# tracker03-12.net
KiCad netlist of a schematic drawn in EAGLE
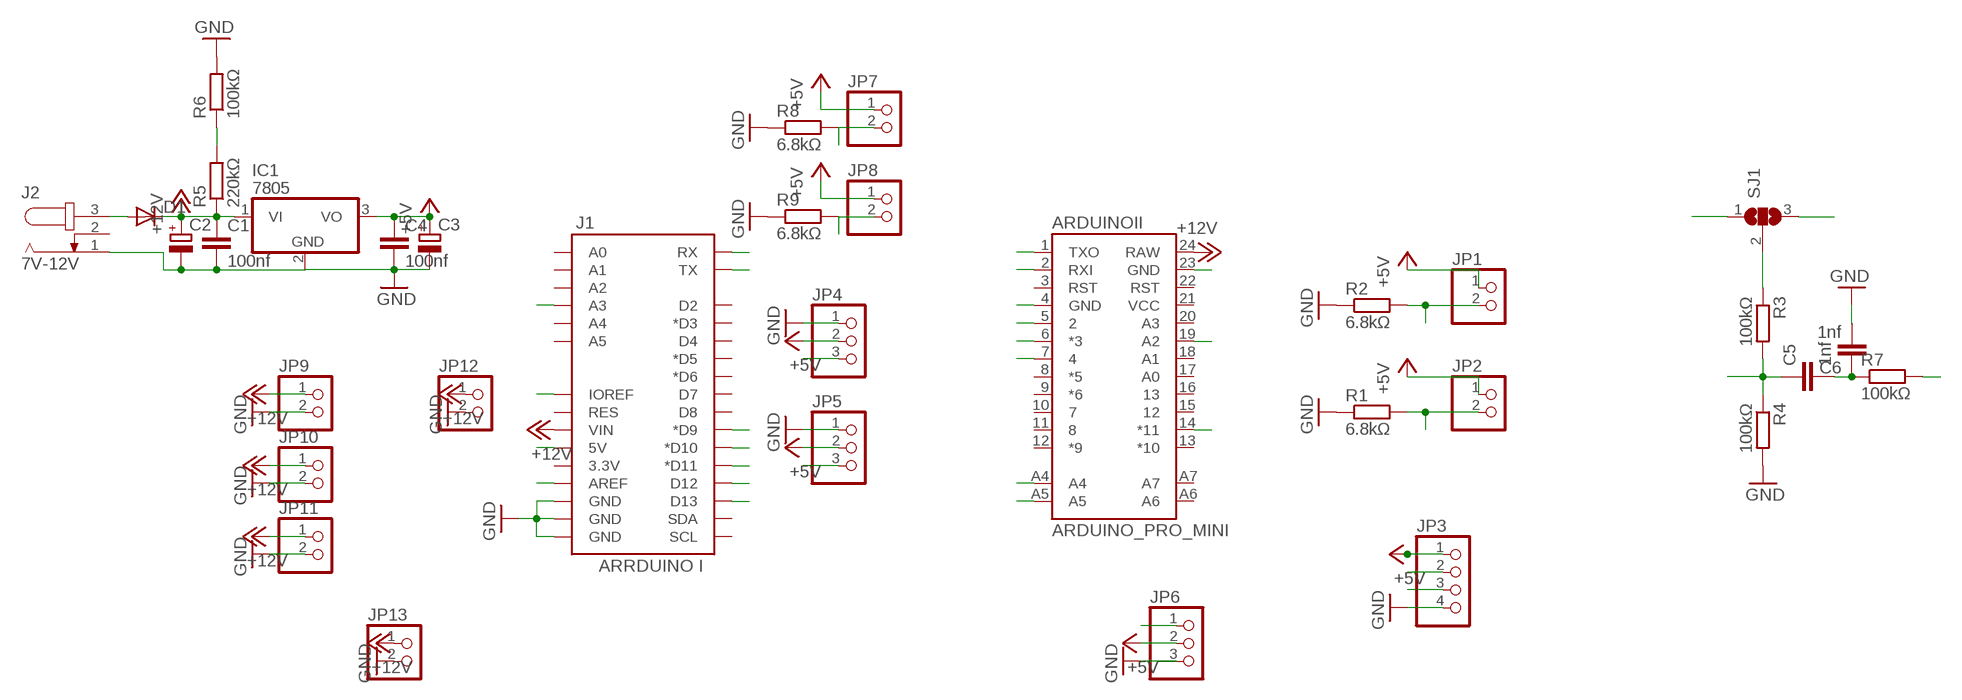
[diagram p0: schematic, sheet 1]

(export (version "E")
  (design (tool "Eeschema 10.0.6"))
  (components
    (comp (ref "ARDUINOII")
      (value "ARDUINO_PRO_MINI")
      (footprint "eagle-import:ARDUINO_PRO_MINI")
      (libsource (lib "eagle-import") (part "ARDUINO_PRO_MINI"))
    )
    (comp (ref "C1")
      (value "100nf")
      (footprint "eagle-import:C050-025X075")
      (libsource (lib "eagle-import") (part "C-EU050-025X075"))
    )
    (comp (ref "C2")
      (value "CPOL-EUE3.5-8")
      (footprint "eagle-import:E3,5-8")
      (libsource (lib "eagle-import") (part "CPOL-EUE3.5-8"))
    )
    (comp (ref "C3")
      (value "CPOL-EUE2.5-5")
      (footprint "eagle-import:E2,5-5")
      (libsource (lib "eagle-import") (part "CPOL-EUE2.5-5"))
    )
    (comp (ref "C4")
      (value "100nf")
      (footprint "eagle-import:C050-025X075")
      (libsource (lib "eagle-import") (part "C-EU050-025X075"))
    )
    (comp (ref "C5")
      (value "1nf")
      (footprint "eagle-import:C050-025X075")
      (libsource (lib "eagle-import") (part "C-EU050-025X075"))
    )
    (comp (ref "C6")
      (value "1nf")
      (footprint "eagle-import:C050-025X075")
      (libsource (lib "eagle-import") (part "C-EU050-025X075"))
    )
    (comp (ref "D1")
      (value "1N4004")
      (footprint "eagle-import:DO41-10")
      (libsource (lib "eagle-import") (part "1N4004"))
    )
    (comp (ref "IC1")
      (value "7805")
      (footprint "eagle-import:TO220V")
      (libsource (lib "eagle-import") (part "78TV05"))
    )
    (comp (ref "J1")
      (value "ARRDUINO I")
      (footprint "eagle-import:UNO_R3_SHIELD_NOLABELS")
      (libsource (lib "eagle-import") (part "ARDUINO_R3_SHIELDNOLABELS"))
    )
    (comp (ref "J2")
      (value "7V-12V")
      (footprint "eagle-import:SPC4077")
      (libsource (lib "eagle-import") (part "JACK-PLUG0"))
    )
    (comp (ref "JP1")
      (value "PINHD-1X2")
      (footprint "eagle-import:1X02")
      (libsource (lib "eagle-import") (part "PINHD-1X2"))
    )
    (comp (ref "JP2")
      (value "PINHD-1X2")
      (footprint "eagle-import:1X02")
      (libsource (lib "eagle-import") (part "PINHD-1X2"))
    )
    (comp (ref "JP3")
      (value "PINHD-1X4")
      (footprint "eagle-import:1X04")
      (libsource (lib "eagle-import") (part "PINHD-1X4"))
    )
    (comp (ref "JP4")
      (value "PINHD-1X3")
      (footprint "eagle-import:1X03")
      (libsource (lib "eagle-import") (part "PINHD-1X3"))
    )
    (comp (ref "JP5")
      (value "PINHD-1X3")
      (footprint "eagle-import:1X03")
      (libsource (lib "eagle-import") (part "PINHD-1X3"))
    )
    (comp (ref "JP6")
      (value "PINHD-1X3")
      (footprint "eagle-import:1X03")
      (libsource (lib "eagle-import") (part "PINHD-1X3"))
    )
    (comp (ref "JP7")
      (value "PINHD-1X2")
      (footprint "eagle-import:1X02")
      (libsource (lib "eagle-import") (part "PINHD-1X2"))
    )
    (comp (ref "JP8")
      (value "PINHD-1X2")
      (footprint "eagle-import:1X02")
      (libsource (lib "eagle-import") (part "PINHD-1X2"))
    )
    (comp (ref "JP9")
      (value "PINHD-1X2")
      (footprint "eagle-import:1X02")
      (libsource (lib "eagle-import") (part "PINHD-1X2"))
    )
    (comp (ref "JP10")
      (value "PINHD-1X2")
      (footprint "eagle-import:1X02")
      (libsource (lib "eagle-import") (part "PINHD-1X2"))
    )
    (comp (ref "JP11")
      (value "PINHD-1X2")
      (footprint "eagle-import:1X02")
      (libsource (lib "eagle-import") (part "PINHD-1X2"))
    )
    (comp (ref "JP12")
      (value "PINHD-1X2")
      (footprint "eagle-import:1X02")
      (libsource (lib "eagle-import") (part "PINHD-1X2"))
    )
    (comp (ref "JP13")
      (value "PINHD-1X2")
      (footprint "eagle-import:1X02")
      (libsource (lib "eagle-import") (part "PINHD-1X2"))
    )
    (comp (ref "R1")
      (value "6.8kΩ")
      (footprint "eagle-import:0204V")
      (libsource (lib "eagle-import") (part "R-EU_0204/2V"))
    )
    (comp (ref "R2")
      (value "6.8kΩ")
      (footprint "eagle-import:0204V")
      (libsource (lib "eagle-import") (part "R-EU_0204/2V"))
    )
    (comp (ref "R3")
      (value "100kΩ")
      (footprint "eagle-import:0204V")
      (libsource (lib "eagle-import") (part "R-EU_0204/2V"))
    )
    (comp (ref "R4")
      (value "100kΩ")
      (footprint "eagle-import:0204V")
      (libsource (lib "eagle-import") (part "R-EU_0204/2V"))
    )
    (comp (ref "R5")
      (value "220kΩ")
      (footprint "eagle-import:0204V")
      (libsource (lib "eagle-import") (part "R-EU_0204/2V"))
    )
    (comp (ref "R6")
      (value "100kΩ")
      (footprint "eagle-import:0204V")
      (libsource (lib "eagle-import") (part "R-EU_0204/2V"))
    )
    (comp (ref "R7")
      (value "100kΩ")
      (footprint "eagle-import:0204V")
      (libsource (lib "eagle-import") (part "R-EU_0204/2V"))
    )
    (comp (ref "R8")
      (value "6.8kΩ")
      (footprint "eagle-import:0204V")
      (libsource (lib "eagle-import") (part "R-EU_0204/2V"))
    )
    (comp (ref "R9")
      (value "6.8kΩ")
      (footprint "eagle-import:0204V")
      (libsource (lib "eagle-import") (part "R-EU_0204/2V"))
    )
    (comp (ref "SJ1")
      (value "SJ2W")
      (footprint "eagle-import:SJ_2")
      (libsource (lib "eagle-import") (part "SJ2W"))
    )
  )
  (nets
    (net (code "1") (name "+5V") (class "Default")
      (node (ref "C3") (pin "+") (pinfunction "+_+") (pintype "passive"))
      (node (ref "C4") (pin "1") (pinfunction "1_1") (pintype "passive"))
      (node (ref "IC1") (pin "3") (pinfunction "VO_3") (pintype "passive"))
      (node (ref "JP1") (pin "1") (pinfunction "1_1") (pintype "passive"))
      (node (ref "JP2") (pin "1") (pinfunction "1_1") (pintype "passive"))
      (node (ref "JP3") (pin "1") (pinfunction "1_1") (pintype "passive"))
      (node (ref "JP4") (pin "2") (pinfunction "2_2") (pintype "passive"))
      (node (ref "JP5") (pin "2") (pinfunction "2_2") (pintype "passive"))
      (node (ref "JP6") (pin "2") (pinfunction "2_2") (pintype "passive"))
      (node (ref "JP7") (pin "1") (pinfunction "1_1") (pintype "passive"))
      (node (ref "JP8") (pin "1") (pinfunction "1_1") (pintype "passive"))
    )
    (net (code "2") (name "+12V") (class "Default")
      (node (ref "ARDUINOII") (pin "24") (pinfunction "RAW_24") (pintype "bidirectional"))
      (node (ref "C1") (pin "1") (pinfunction "1_1") (pintype "passive"))
      (node (ref "C2") (pin "+") (pinfunction "+_+") (pintype "passive"))
      (node (ref "D1") (pin "C") (pinfunction "C_C") (pintype "passive"))
      (node (ref "IC1") (pin "1") (pinfunction "VI_1") (pintype "input"))
      (node (ref "J1") (pin "VIN") (pinfunction "VIN_VIN") (pintype "bidirectional"))
      (node (ref "JP10") (pin "1") (pinfunction "1_1") (pintype "passive"))
      (node (ref "JP11") (pin "1") (pinfunction "1_1") (pintype "passive"))
      (node (ref "JP12") (pin "1") (pinfunction "1_1") (pintype "passive"))
      (node (ref "JP13") (pin "1") (pinfunction "1_1") (pintype "passive"))
      (node (ref "JP9") (pin "1") (pinfunction "1_1") (pintype "passive"))
      (node (ref "R5") (pin "1") (pinfunction "1_1") (pintype "passive"))
    )
    (net (code "3") (name "/5VA") (class "Default")
      (node (ref "J1") (pin "5V") (pinfunction "5V_5V") (pintype "bidirectional"))
      (node (ref "SJ1") (pin "3") (pinfunction "3_3") (pintype "passive"))
    )
    (net (code "4") (name "/A2") (class "Default")
      (node (ref "ARDUINOII") (pin "19") (pinfunction "A2_19") (pintype "bidirectional"))
      (node (ref "R5") (pin "2") (pinfunction "2_2") (pintype "passive"))
      (node (ref "R6") (pin "1") (pinfunction "1_1") (pintype "passive"))
    )
    (net (code "5") (name "/A3") (class "Default")
      (node (ref "C5") (pin "1") (pinfunction "1_1") (pintype "passive"))
      (node (ref "J1") (pin "A3") (pinfunction "A3_A3") (pintype "bidirectional"))
      (node (ref "R3") (pin "2") (pinfunction "2_2") (pintype "passive"))
      (node (ref "R4") (pin "1") (pinfunction "1_1") (pintype "passive"))
    )
    (net (code "6") (name "/A4") (class "Default")
      (node (ref "ARDUINOII") (pin "A4") (pinfunction "A4_A4") (pintype "bidirectional"))
      (node (ref "JP3") (pin "2") (pinfunction "2_2") (pintype "passive"))
    )
    (net (code "7") (name "/A5") (class "Default")
      (node (ref "ARDUINOII") (pin "A5") (pinfunction "A5_A5") (pintype "bidirectional"))
      (node (ref "JP3") (pin "3") (pinfunction "3_3") (pintype "passive"))
    )
    (net (code "8") (name "/AREF") (class "Default")
      (node (ref "J1") (pin "AREF") (pinfunction "AREF_AREF") (pintype "bidirectional"))
      (node (ref "SJ1") (pin "1") (pinfunction "1_1") (pintype "passive"))
    )
    (net (code "9") (name "/D2") (class "Default")
      (node (ref "ARDUINOII") (pin "5") (pinfunction "2_5") (pintype "bidirectional"))
      (node (ref "JP1") (pin "2") (pinfunction "2_2") (pintype "passive"))
      (node (ref "R2") (pin "2") (pinfunction "2_2") (pintype "passive"))
    )
    (net (code "10") (name "/D4") (class "Default")
      (node (ref "ARDUINOII") (pin "7") (pinfunction "4_7") (pintype "bidirectional"))
      (node (ref "JP2") (pin "2") (pinfunction "2_2") (pintype "passive"))
      (node (ref "R1") (pin "2") (pinfunction "2_2") (pintype "passive"))
    )
    (net (code "11") (name "/D9") (class "Default")
      (node (ref "J1") (pin "D9") (pinfunction "*D9_D9") (pintype "bidirectional"))
      (node (ref "JP4") (pin "3") (pinfunction "3_3") (pintype "passive"))
    )
    (net (code "12") (name "/D10") (class "Default")
      (node (ref "J1") (pin "D10") (pinfunction "*D10_D10") (pintype "bidirectional"))
      (node (ref "JP5") (pin "3") (pinfunction "3_3") (pintype "passive"))
    )
    (net (code "13") (name "/D11") (class "Default")
      (node (ref "ARDUINOII") (pin "14") (pinfunction "*11_14") (pintype "bidirectional"))
      (node (ref "JP6") (pin "1") (pinfunction "1_1") (pintype "passive"))
    )
    (net (code "14") (name "/D11A1") (class "Default")
      (node (ref "J1") (pin "D11") (pinfunction "*D11_D11") (pintype "bidirectional"))
      (node (ref "JP7") (pin "2") (pinfunction "2_2") (pintype "passive"))
      (node (ref "R8") (pin "2") (pinfunction "2_2") (pintype "passive"))
    )
    (net (code "15") (name "/D12") (class "Default")
      (node (ref "J1") (pin "D12") (pinfunction "D12_D12") (pintype "bidirectional"))
      (node (ref "JP8") (pin "2") (pinfunction "2_2") (pintype "passive"))
      (node (ref "R9") (pin "2") (pinfunction "2_2") (pintype "passive"))
    )
    (net (code "16") (name "/RX") (class "Default")
      (node (ref "ARDUINOII") (pin "1") (pinfunction "TXO_1") (pintype "bidirectional"))
      (node (ref "J1") (pin "RX") (pinfunction "RX_RX") (pintype "bidirectional"))
    )
    (net (code "17") (name "/TX") (class "Default")
      (node (ref "ARDUINOII") (pin "2") (pinfunction "RXI_2") (pintype "bidirectional"))
      (node (ref "J1") (pin "TX") (pinfunction "TX_TX") (pintype "bidirectional"))
    )
    (net (code "18") (name "GND") (class "Default")
      (node (ref "ARDUINOII") (pin "23") (pinfunction "GND_23") (pintype "bidirectional"))
      (node (ref "ARDUINOII") (pin "4") (pinfunction "GND_4") (pintype "bidirectional"))
      (node (ref "C1") (pin "2") (pinfunction "2_2") (pintype "passive"))
      (node (ref "C2") (pin "-") (pinfunction "-_-") (pintype "passive"))
      (node (ref "C3") (pin "-") (pinfunction "-_-") (pintype "passive"))
      (node (ref "C4") (pin "2") (pinfunction "2_2") (pintype "passive"))
      (node (ref "C6") (pin "2") (pinfunction "2_2") (pintype "passive"))
      (node (ref "IC1") (pin "2") (pinfunction "GND_2") (pintype "passive"))
      (node (ref "J1") (pin "GND@0") (pinfunction "GND_GND@0") (pintype "bidirectional"))
      (node (ref "J1") (pin "GND@1") (pinfunction "GND_GND@1") (pintype "bidirectional"))
      (node (ref "J1") (pin "GND@2") (pinfunction "GND_GND@2") (pintype "bidirectional"))
      (node (ref "J2") (pin "1") (pinfunction "1_1") (pintype "passive"))
      (node (ref "JP10") (pin "2") (pinfunction "2_2") (pintype "passive"))
      (node (ref "JP11") (pin "2") (pinfunction "2_2") (pintype "passive"))
      (node (ref "JP12") (pin "2") (pinfunction "2_2") (pintype "passive"))
      (node (ref "JP13") (pin "2") (pinfunction "2_2") (pintype "passive"))
      (node (ref "JP3") (pin "4") (pinfunction "4_4") (pintype "passive"))
      (node (ref "JP4") (pin "1") (pinfunction "1_1") (pintype "passive"))
      (node (ref "JP5") (pin "1") (pinfunction "1_1") (pintype "passive"))
      (node (ref "JP6") (pin "3") (pinfunction "3_3") (pintype "passive"))
      (node (ref "JP9") (pin "2") (pinfunction "2_2") (pintype "passive"))
      (node (ref "R1") (pin "1") (pinfunction "1_1") (pintype "passive"))
      (node (ref "R2") (pin "1") (pinfunction "1_1") (pintype "passive"))
      (node (ref "R4") (pin "2") (pinfunction "2_2") (pintype "passive"))
      (node (ref "R6") (pin "2") (pinfunction "2_2") (pintype "passive"))
      (node (ref "R8") (pin "1") (pinfunction "1_1") (pintype "passive"))
      (node (ref "R9") (pin "1") (pinfunction "1_1") (pintype "passive"))
    )
    (net (code "19") (name "Net-(C5-Pad2)") (class "Default")
      (node (ref "C5") (pin "2") (pinfunction "2_2") (pintype "passive"))
      (node (ref "C6") (pin "1") (pinfunction "1_1") (pintype "passive"))
      (node (ref "R7") (pin "1") (pinfunction "1_1") (pintype "passive"))
    )
    (net (code "20") (name "Net-(D1-PadA)") (class "Default")
      (node (ref "D1") (pin "A") (pinfunction "A_A") (pintype "passive"))
      (node (ref "J2") (pin "3") (pinfunction "3_3") (pintype "passive"))
    )
    (net (code "21") (name "Net-(R3-Pad1)") (class "Default")
      (node (ref "R3") (pin "1") (pinfunction "1_1") (pintype "passive"))
      (node (ref "SJ1") (pin "2") (pinfunction "2_2") (pintype "passive"))
    )
    (net (code "22") (name "unconnected-(ARDUINOII-*3-Pad6)") (class "Default")
      (node (ref "ARDUINOII") (pin "6") (pinfunction "*3_6") (pintype "bidirectional"))
    )
    (net (code "23") (name "unconnected-(ARDUINOII-*5-Pad8)") (class "Default")
      (node (ref "ARDUINOII") (pin "8") (pinfunction "*5_8") (pintype "bidirectional"))
    )
    (net (code "24") (name "unconnected-(ARDUINOII-*6-Pad9)") (class "Default")
      (node (ref "ARDUINOII") (pin "9") (pinfunction "*6_9") (pintype "bidirectional"))
    )
    (net (code "25") (name "unconnected-(ARDUINOII-*9-Pad12)") (class "Default")
      (node (ref "ARDUINOII") (pin "12") (pinfunction "*9_12") (pintype "bidirectional"))
    )
    (net (code "26") (name "unconnected-(ARDUINOII-*10-Pad13)") (class "Default")
      (node (ref "ARDUINOII") (pin "13") (pinfunction "*10_13") (pintype "bidirectional"))
    )
    (net (code "27") (name "unconnected-(ARDUINOII-7-Pad10)") (class "Default")
      (node (ref "ARDUINOII") (pin "10") (pinfunction "7_10") (pintype "bidirectional"))
    )
    (net (code "28") (name "unconnected-(ARDUINOII-8-Pad11)") (class "Default")
      (node (ref "ARDUINOII") (pin "11") (pinfunction "8_11") (pintype "bidirectional"))
    )
    (net (code "29") (name "unconnected-(ARDUINOII-12-Pad15)") (class "Default")
      (node (ref "ARDUINOII") (pin "15") (pinfunction "12_15") (pintype "bidirectional"))
    )
    (net (code "30") (name "unconnected-(ARDUINOII-13-Pad16)") (class "Default")
      (node (ref "ARDUINOII") (pin "16") (pinfunction "13_16") (pintype "bidirectional"))
    )
    (net (code "31") (name "unconnected-(ARDUINOII-A0-Pad17)") (class "Default")
      (node (ref "ARDUINOII") (pin "17") (pinfunction "A0_17") (pintype "bidirectional"))
    )
    (net (code "32") (name "unconnected-(ARDUINOII-A1-Pad18)") (class "Default")
      (node (ref "ARDUINOII") (pin "18") (pinfunction "A1_18") (pintype "bidirectional"))
    )
    (net (code "33") (name "unconnected-(ARDUINOII-A3-Pad20)") (class "Default")
      (node (ref "ARDUINOII") (pin "20") (pinfunction "A3_20") (pintype "bidirectional"))
    )
    (net (code "34") (name "unconnected-(ARDUINOII-PadA6)") (class "Default")
      (node (ref "ARDUINOII") (pin "A6") (pinfunction "A6_A6") (pintype "bidirectional"))
    )
    (net (code "35") (name "unconnected-(ARDUINOII-PadA7)") (class "Default")
      (node (ref "ARDUINOII") (pin "A7") (pinfunction "A7_A7") (pintype "bidirectional"))
    )
    (net (code "36") (name "unconnected-(ARDUINOII-RST-Pad3)") (class "Default")
      (node (ref "ARDUINOII") (pin "3") (pinfunction "RST_3") (pintype "bidirectional"))
    )
    (net (code "37") (name "unconnected-(ARDUINOII-RST-Pad22)") (class "Default")
      (node (ref "ARDUINOII") (pin "22") (pinfunction "RST_22") (pintype "bidirectional"))
    )
    (net (code "38") (name "unconnected-(ARDUINOII-VCC-Pad21)") (class "Default")
      (node (ref "ARDUINOII") (pin "21") (pinfunction "VCC_21") (pintype "bidirectional"))
    )
    (net (code "39") (name "unconnected-(J1-*D3-PadD3)") (class "Default")
      (node (ref "J1") (pin "D3") (pinfunction "*D3_D3") (pintype "bidirectional"))
    )
    (net (code "40") (name "unconnected-(J1-*D5-PadD5)") (class "Default")
      (node (ref "J1") (pin "D5") (pinfunction "*D5_D5") (pintype "bidirectional"))
    )
    (net (code "41") (name "unconnected-(J1-*D6-PadD6)") (class "Default")
      (node (ref "J1") (pin "D6") (pinfunction "*D6_D6") (pintype "bidirectional"))
    )
    (net (code "42") (name "unconnected-(J1-Pad3.3V)") (class "Default")
      (node (ref "J1") (pin "3.3V") (pinfunction "3.3V_3.3V") (pintype "bidirectional"))
    )
    (net (code "43") (name "unconnected-(J1-PadA0)") (class "Default")
      (node (ref "J1") (pin "A0") (pinfunction "A0_A0") (pintype "bidirectional"))
    )
    (net (code "44") (name "unconnected-(J1-PadA1)") (class "Default")
      (node (ref "J1") (pin "A1") (pinfunction "A1_A1") (pintype "bidirectional"))
    )
    (net (code "45") (name "unconnected-(J1-PadA2)") (class "Default")
      (node (ref "J1") (pin "A2") (pinfunction "A2_A2") (pintype "bidirectional"))
    )
    (net (code "46") (name "unconnected-(J1-PadA4)") (class "Default")
      (node (ref "J1") (pin "A4") (pinfunction "A4_A4") (pintype "bidirectional"))
    )
    (net (code "47") (name "unconnected-(J1-PadA5)") (class "Default")
      (node (ref "J1") (pin "A5") (pinfunction "A5_A5") (pintype "bidirectional"))
    )
    (net (code "48") (name "unconnected-(J1-PadD2)") (class "Default")
      (node (ref "J1") (pin "D2") (pinfunction "D2_D2") (pintype "bidirectional"))
    )
    (net (code "49") (name "unconnected-(J1-PadD4)") (class "Default")
      (node (ref "J1") (pin "D4") (pinfunction "D4_D4") (pintype "bidirectional"))
    )
    (net (code "50") (name "unconnected-(J1-PadD7)") (class "Default")
      (node (ref "J1") (pin "D7") (pinfunction "D7_D7") (pintype "bidirectional"))
    )
    (net (code "51") (name "unconnected-(J1-PadD8)") (class "Default")
      (node (ref "J1") (pin "D8") (pinfunction "D8_D8") (pintype "bidirectional"))
    )
    (net (code "52") (name "unconnected-(J1-PadD13)") (class "Default")
      (node (ref "J1") (pin "D13") (pinfunction "D13_D13") (pintype "bidirectional"))
    )
    (net (code "53") (name "unconnected-(J1-PadIOREF)") (class "Default")
      (node (ref "J1") (pin "IOREF") (pinfunction "IOREF_IOREF") (pintype "bidirectional"))
    )
    (net (code "54") (name "unconnected-(J1-PadRES)") (class "Default")
      (node (ref "J1") (pin "RES") (pinfunction "RES_RES") (pintype "bidirectional"))
    )
    (net (code "55") (name "unconnected-(J1-PadSCL)") (class "Default")
      (node (ref "J1") (pin "SCL") (pinfunction "SCL_SCL") (pintype "bidirectional"))
    )
    (net (code "56") (name "unconnected-(J1-PadSDA)") (class "Default")
      (node (ref "J1") (pin "SDA") (pinfunction "SDA_SDA") (pintype "bidirectional"))
    )
    (net (code "57") (name "unconnected-(J2-Pad2)") (class "Default")
      (node (ref "J2") (pin "2") (pinfunction "2_2") (pintype "passive"))
    )
    (net (code "58") (name "unconnected-(R7-Pad2)") (class "Default")
      (node (ref "R7") (pin "2") (pinfunction "2_2") (pintype "passive"))
    )
  )
)
